# UltiMem64_v1.net
KiCad netlist of a schematic drawn in EAGLE
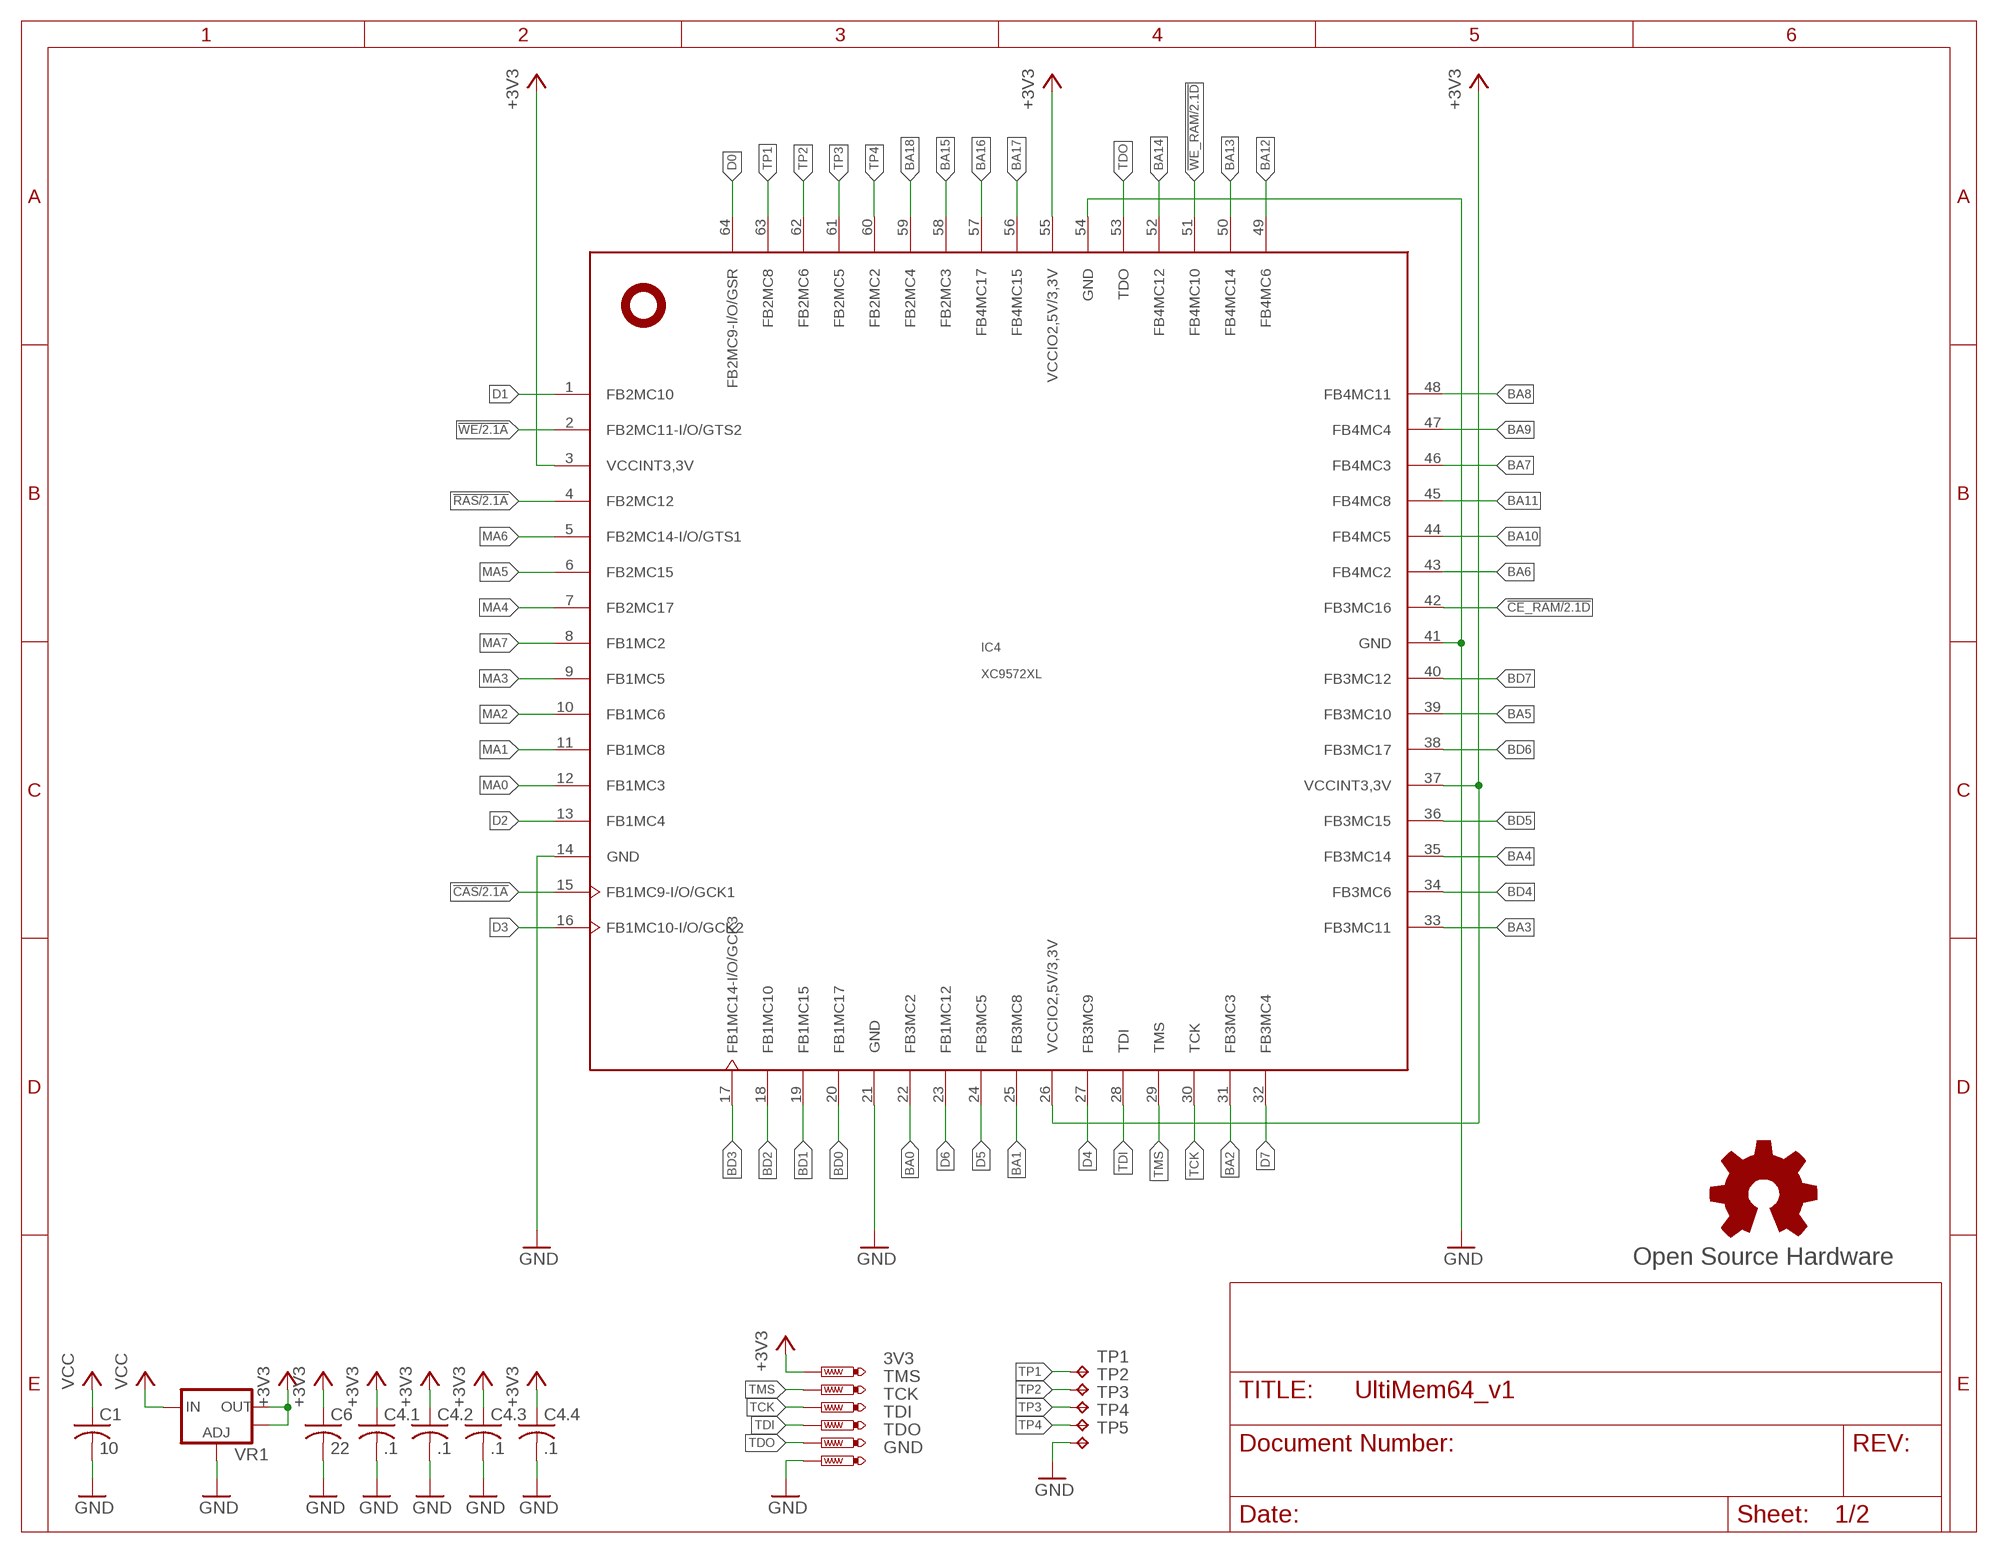
[diagram p0: schematic, sheet 1]
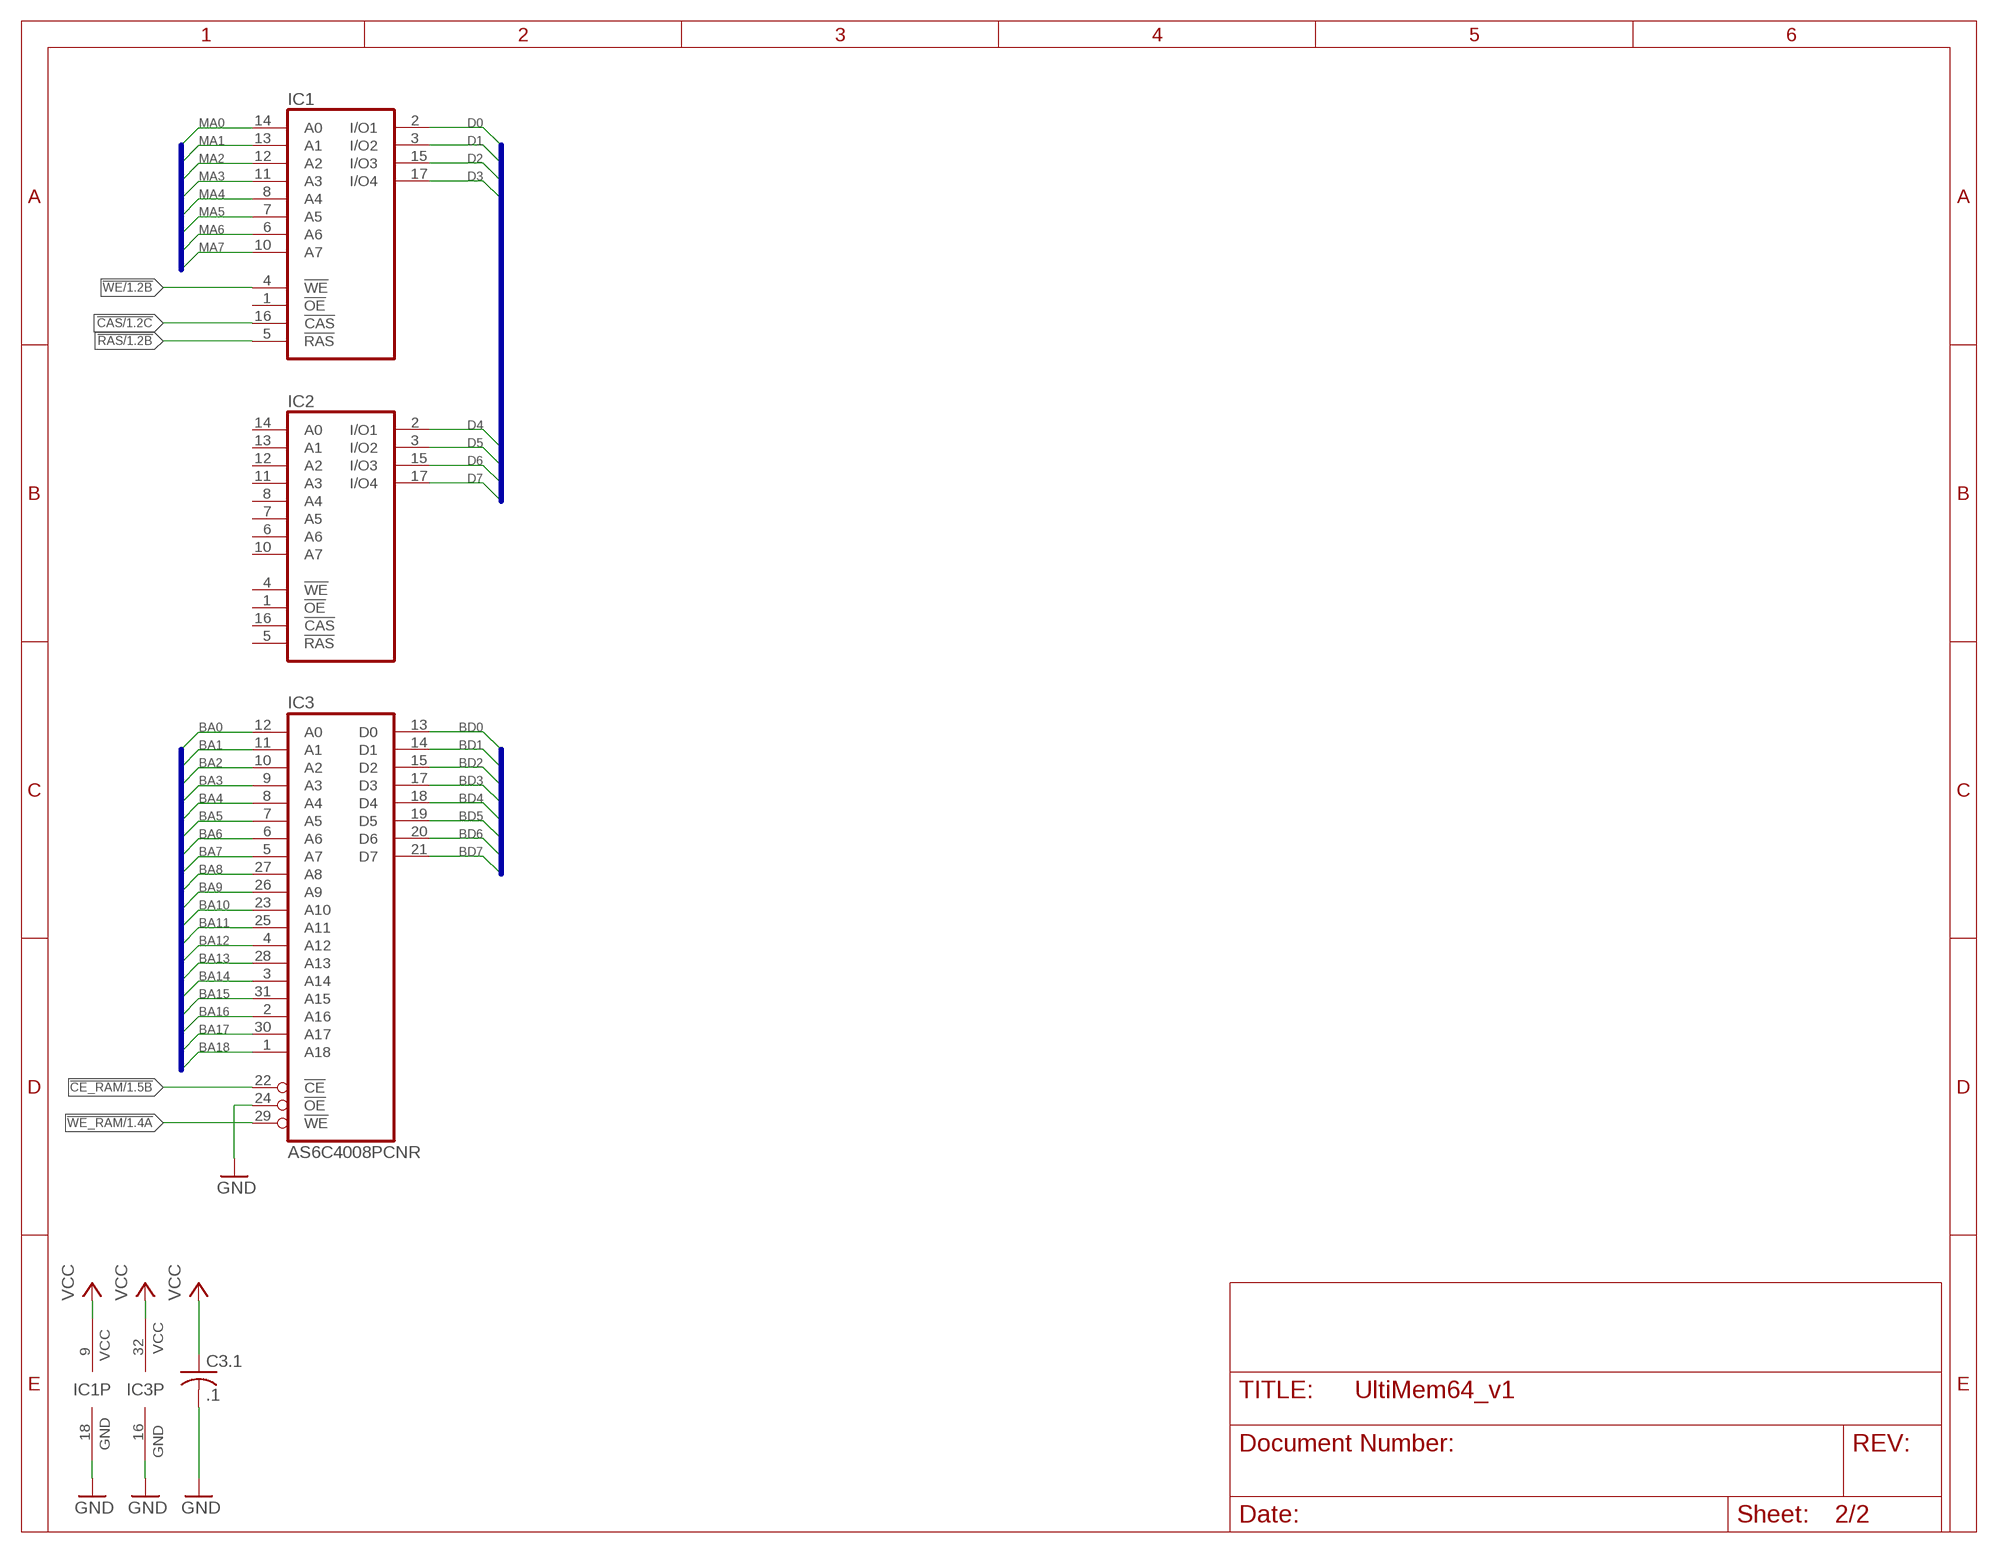
[diagram p1: schematic, sheet 2]

(export (version "E")
  (design (tool "Eeschema 10.0.6"))
  (components
    (comp (ref "3V3")
      (value "PTR1TP08R")
      (footprint "eagle-import:TP08R")
      (libsource (lib "eagle-import") (part "PTR1TP08R"))
    )
    (comp (ref "C1")
      (value "10")
      (footprint "eagle-import:C0805")
      (libsource (lib "eagle-import") (part "C-USC0805"))
    )
    (comp (ref "C4.1")
      (value ".1")
      (footprint "eagle-import:C0402")
      (libsource (lib "eagle-import") (part "C-USC0402"))
    )
    (comp (ref "C4.2")
      (value ".1")
      (footprint "eagle-import:C0402")
      (libsource (lib "eagle-import") (part "C-USC0402"))
    )
    (comp (ref "C4.3")
      (value ".1")
      (footprint "eagle-import:C0402")
      (libsource (lib "eagle-import") (part "C-USC0402"))
    )
    (comp (ref "C4.4")
      (value ".1")
      (footprint "eagle-import:C0402")
      (libsource (lib "eagle-import") (part "C-USC0402"))
    )
    (comp (ref "C6")
      (value "22")
      (footprint "eagle-import:C0805")
      (libsource (lib "eagle-import") (part "C-USC0805"))
    )
    (comp (ref "GND")
      (value "PTR1TP08R")
      (footprint "eagle-import:TP08R")
      (libsource (lib "eagle-import") (part "PTR1TP08R"))
    )
    (comp (ref "GOLD_ORB_SM1")
      (value "Open Source Hardware")
      (footprint "eagle-import:OSHW_5MM")
      (libsource (lib "eagle-import") (part "OSHWLOGOLOGO5MM"))
    )
    (comp (ref "IC4")
      (value "XC9572XL")
      (footprint "eagle-import:VQFP64")
      (libsource (lib "eagle-import") (part "XC9572XLVQG64"))
    )
    (comp (ref "TCK")
      (value "PTR1TP08R")
      (footprint "eagle-import:TP08R")
      (libsource (lib "eagle-import") (part "PTR1TP08R"))
    )
    (comp (ref "TDI")
      (value "PTR1TP08R")
      (footprint "eagle-import:TP08R")
      (libsource (lib "eagle-import") (part "PTR1TP08R"))
    )
    (comp (ref "TDO")
      (value "PTR1TP08R")
      (footprint "eagle-import:TP08R")
      (libsource (lib "eagle-import") (part "PTR1TP08R"))
    )
    (comp (ref "TMS")
      (value "PTR1TP08R")
      (footprint "eagle-import:TP08R")
      (libsource (lib "eagle-import") (part "PTR1TP08R"))
    )
    (comp (ref "TP1")
      (value "TPPAD1-13")
      (footprint "eagle-import:P1-13")
      (libsource (lib "eagle-import") (part "TPPAD1-13"))
    )
    (comp (ref "TP2")
      (value "TPPAD1-13")
      (footprint "eagle-import:P1-13")
      (libsource (lib "eagle-import") (part "TPPAD1-13"))
    )
    (comp (ref "TP3")
      (value "TPPAD1-13")
      (footprint "eagle-import:P1-13")
      (libsource (lib "eagle-import") (part "TPPAD1-13"))
    )
    (comp (ref "TP4")
      (value "TPPAD1-13")
      (footprint "eagle-import:P1-13")
      (libsource (lib "eagle-import") (part "TPPAD1-13"))
    )
    (comp (ref "TP5")
      (value "TPPAD1-13")
      (footprint "eagle-import:P1-13")
      (libsource (lib "eagle-import") (part "TPPAD1-13"))
    )
    (comp (ref "VR1")
      (value "V_REG_LM1117SOT223")
      (footprint "eagle-import:SOT223")
      (libsource (lib "eagle-import") (part "V_REG_LM1117SOT223"))
    )
    (comp (ref "C3.1")
      (value ".1")
      (footprint "eagle-import:C0402")
      (libsource (lib "eagle-import") (part "C-USC0402"))
    )
    (comp (ref "IC1")
      (value "41464C-HDR")
      (footprint "eagle-import:DIL18_REV")
      (libsource (lib "eagle-import") (part "41464C-HDR"))
    )
    (comp (ref "IC2")
      (value "41464C-HDR")
      (footprint "eagle-import:DIL18_REV")
      (libsource (lib "eagle-import") (part "41464C-HDR"))
    )
    (comp (ref "IC3")
      (value "AS6C4008PCNR")
      (footprint "eagle-import:DIL32-RP")
      (libsource (lib "eagle-import") (part "AS6C4008PCNR"))
    )
  )
  (nets
    (net (code "1") (name "+3V3") (class "Default")
      (node (ref "3V3") (pin "TP") (pinfunction "TP_TP") (pintype "input"))
      (node (ref "C4.1") (pin "1") (pinfunction "1_1") (pintype "passive"))
      (node (ref "C4.2") (pin "1") (pinfunction "1_1") (pintype "passive"))
      (node (ref "C4.3") (pin "1") (pinfunction "1_1") (pintype "passive"))
      (node (ref "C4.4") (pin "1") (pinfunction "1_1") (pintype "passive"))
      (node (ref "C6") (pin "1") (pinfunction "1_1") (pintype "passive"))
      (node (ref "IC4") (pin "26") (pinfunction "VCCIO2,5V/3,3V_26") (pintype "power_in"))
      (node (ref "IC4") (pin "3") (pinfunction "VCCINT3,3V_3") (pintype "power_in"))
      (node (ref "IC4") (pin "37") (pinfunction "VCCINT3,3V_37") (pintype "power_in"))
      (node (ref "IC4") (pin "55") (pinfunction "VCCIO2,5V/3,3V_55") (pintype "power_in"))
      (node (ref "VR1") (pin "2") (pinfunction "OUT_2") (pintype "output"))
      (node (ref "VR1") (pin "4") (pinfunction "OUT_4") (pintype "output"))
    )
    (net (code "2") (name "BA0") (class "Default")
      (node (ref "IC3") (pin "12") (pinfunction "A0_12") (pintype "input"))
      (node (ref "IC4") (pin "22") (pinfunction "FB3MC2_22") (pintype "bidirectional"))
    )
    (net (code "3") (name "BA1") (class "Default")
      (node (ref "IC3") (pin "11") (pinfunction "A1_11") (pintype "input"))
      (node (ref "IC4") (pin "25") (pinfunction "FB3MC8_25") (pintype "bidirectional"))
    )
    (net (code "4") (name "BA2") (class "Default")
      (node (ref "IC3") (pin "10") (pinfunction "A2_10") (pintype "input"))
      (node (ref "IC4") (pin "31") (pinfunction "FB3MC3_31") (pintype "bidirectional"))
    )
    (net (code "5") (name "BA3") (class "Default")
      (node (ref "IC3") (pin "9") (pinfunction "A3_9") (pintype "input"))
      (node (ref "IC4") (pin "33") (pinfunction "FB3MC11_33") (pintype "bidirectional"))
    )
    (net (code "6") (name "BA4") (class "Default")
      (node (ref "IC3") (pin "8") (pinfunction "A4_8") (pintype "input"))
      (node (ref "IC4") (pin "35") (pinfunction "FB3MC14_35") (pintype "bidirectional"))
    )
    (net (code "7") (name "BA5") (class "Default")
      (node (ref "IC3") (pin "7") (pinfunction "A5_7") (pintype "input"))
      (node (ref "IC4") (pin "39") (pinfunction "FB3MC10_39") (pintype "bidirectional"))
    )
    (net (code "8") (name "BA6") (class "Default")
      (node (ref "IC3") (pin "6") (pinfunction "A6_6") (pintype "input"))
      (node (ref "IC4") (pin "43") (pinfunction "FB4MC2_43") (pintype "bidirectional"))
    )
    (net (code "9") (name "BA7") (class "Default")
      (node (ref "IC3") (pin "5") (pinfunction "A7_5") (pintype "input"))
      (node (ref "IC4") (pin "46") (pinfunction "FB4MC3_46") (pintype "bidirectional"))
    )
    (net (code "10") (name "BA8") (class "Default")
      (node (ref "IC3") (pin "27") (pinfunction "A8_27") (pintype "input"))
      (node (ref "IC4") (pin "48") (pinfunction "FB4MC11_48") (pintype "bidirectional"))
    )
    (net (code "11") (name "BA9") (class "Default")
      (node (ref "IC3") (pin "26") (pinfunction "A9_26") (pintype "input"))
      (node (ref "IC4") (pin "47") (pinfunction "FB4MC4_47") (pintype "bidirectional"))
    )
    (net (code "12") (name "BA10") (class "Default")
      (node (ref "IC3") (pin "23") (pinfunction "A10_23") (pintype "input"))
      (node (ref "IC4") (pin "44") (pinfunction "FB4MC5_44") (pintype "bidirectional"))
    )
    (net (code "13") (name "BA11") (class "Default")
      (node (ref "IC3") (pin "25") (pinfunction "A11_25") (pintype "input"))
      (node (ref "IC4") (pin "45") (pinfunction "FB4MC8_45") (pintype "bidirectional"))
    )
    (net (code "14") (name "BA12") (class "Default")
      (node (ref "IC3") (pin "4") (pinfunction "A12_4") (pintype "input"))
      (node (ref "IC4") (pin "49") (pinfunction "FB4MC6_49") (pintype "bidirectional"))
    )
    (net (code "15") (name "BA13") (class "Default")
      (node (ref "IC3") (pin "28") (pinfunction "A13_28") (pintype "input"))
      (node (ref "IC4") (pin "50") (pinfunction "FB4MC14_50") (pintype "bidirectional"))
    )
    (net (code "16") (name "BA14") (class "Default")
      (node (ref "IC3") (pin "3") (pinfunction "A14_3") (pintype "input"))
      (node (ref "IC4") (pin "52") (pinfunction "FB4MC12_52") (pintype "bidirectional"))
    )
    (net (code "17") (name "BA15") (class "Default")
      (node (ref "IC3") (pin "31") (pinfunction "A15_31") (pintype "input"))
      (node (ref "IC4") (pin "58") (pinfunction "FB2MC3_58") (pintype "bidirectional"))
    )
    (net (code "18") (name "BA16") (class "Default")
      (node (ref "IC3") (pin "2") (pinfunction "A16_2") (pintype "input"))
      (node (ref "IC4") (pin "57") (pinfunction "FB4MC17_57") (pintype "bidirectional"))
    )
    (net (code "19") (name "BA17") (class "Default")
      (node (ref "IC3") (pin "30") (pinfunction "A17_30") (pintype "input"))
      (node (ref "IC4") (pin "56") (pinfunction "FB4MC15_56") (pintype "bidirectional"))
    )
    (net (code "20") (name "BA18") (class "Default")
      (node (ref "IC3") (pin "1") (pinfunction "A18_1") (pintype "input"))
      (node (ref "IC4") (pin "59") (pinfunction "FB2MC4_59") (pintype "bidirectional"))
    )
    (net (code "21") (name "BD0") (class "Default")
      (node (ref "IC3") (pin "13") (pinfunction "D0_13") (pintype "bidirectional"))
      (node (ref "IC4") (pin "20") (pinfunction "FB1MC17_20") (pintype "bidirectional"))
    )
    (net (code "22") (name "BD1") (class "Default")
      (node (ref "IC3") (pin "14") (pinfunction "D1_14") (pintype "bidirectional"))
      (node (ref "IC4") (pin "19") (pinfunction "FB1MC15_19") (pintype "bidirectional"))
    )
    (net (code "23") (name "BD2") (class "Default")
      (node (ref "IC3") (pin "15") (pinfunction "D2_15") (pintype "bidirectional"))
      (node (ref "IC4") (pin "18") (pinfunction "FB1MC10_18") (pintype "bidirectional"))
    )
    (net (code "24") (name "BD3") (class "Default")
      (node (ref "IC3") (pin "17") (pinfunction "D3_17") (pintype "bidirectional"))
      (node (ref "IC4") (pin "17") (pinfunction "FB1MC14-I/O/GCK3_17") (pintype "bidirectional"))
    )
    (net (code "25") (name "BD4") (class "Default")
      (node (ref "IC3") (pin "18") (pinfunction "D4_18") (pintype "bidirectional"))
      (node (ref "IC4") (pin "34") (pinfunction "FB3MC6_34") (pintype "bidirectional"))
    )
    (net (code "26") (name "BD5") (class "Default")
      (node (ref "IC3") (pin "19") (pinfunction "D5_19") (pintype "bidirectional"))
      (node (ref "IC4") (pin "36") (pinfunction "FB3MC15_36") (pintype "bidirectional"))
    )
    (net (code "27") (name "BD6") (class "Default")
      (node (ref "IC3") (pin "20") (pinfunction "D6_20") (pintype "bidirectional"))
      (node (ref "IC4") (pin "38") (pinfunction "FB3MC17_38") (pintype "bidirectional"))
    )
    (net (code "28") (name "BD7") (class "Default")
      (node (ref "IC3") (pin "21") (pinfunction "D7_21") (pintype "bidirectional"))
      (node (ref "IC4") (pin "40") (pinfunction "FB3MC12_40") (pintype "bidirectional"))
    )
    (net (code "29") (name "D0") (class "Default")
      (node (ref "IC1") (pin "2") (pinfunction "I/O1_2") (pintype "bidirectional"))
      (node (ref "IC4") (pin "64") (pinfunction "FB2MC9-I/O/GSR_64") (pintype "bidirectional"))
    )
    (net (code "30") (name "D1") (class "Default")
      (node (ref "IC1") (pin "3") (pinfunction "I/O2_3") (pintype "bidirectional"))
      (node (ref "IC4") (pin "1") (pinfunction "FB2MC10_1") (pintype "bidirectional"))
    )
    (net (code "31") (name "D2") (class "Default")
      (node (ref "IC1") (pin "15") (pinfunction "I/O3_15") (pintype "bidirectional"))
      (node (ref "IC4") (pin "13") (pinfunction "FB1MC4_13") (pintype "bidirectional"))
    )
    (net (code "32") (name "D3") (class "Default")
      (node (ref "IC1") (pin "17") (pinfunction "I/O4_17") (pintype "bidirectional"))
      (node (ref "IC4") (pin "16") (pinfunction "FB1MC10-I/O/GCK2_16") (pintype "bidirectional"))
    )
    (net (code "33") (name "D4") (class "Default")
      (node (ref "IC2") (pin "2") (pinfunction "I/O1_2") (pintype "bidirectional"))
      (node (ref "IC4") (pin "27") (pinfunction "FB3MC9_27") (pintype "bidirectional"))
    )
    (net (code "34") (name "D5") (class "Default")
      (node (ref "IC2") (pin "3") (pinfunction "I/O2_3") (pintype "bidirectional"))
      (node (ref "IC4") (pin "24") (pinfunction "FB3MC5_24") (pintype "bidirectional"))
    )
    (net (code "35") (name "D6") (class "Default")
      (node (ref "IC2") (pin "15") (pinfunction "I/O3_15") (pintype "bidirectional"))
      (node (ref "IC4") (pin "23") (pinfunction "FB1MC12_23") (pintype "bidirectional"))
    )
    (net (code "36") (name "D7") (class "Default")
      (node (ref "IC2") (pin "17") (pinfunction "I/O4_17") (pintype "bidirectional"))
      (node (ref "IC4") (pin "32") (pinfunction "FB3MC4_32") (pintype "bidirectional"))
    )
    (net (code "37") (name "GND") (class "Default")
      (node (ref "C1") (pin "2") (pinfunction "2_2") (pintype "passive"))
      (node (ref "C3.1") (pin "2") (pinfunction "2_2") (pintype "passive"))
      (node (ref "C4.1") (pin "2") (pinfunction "2_2") (pintype "passive"))
      (node (ref "C4.2") (pin "2") (pinfunction "2_2") (pintype "passive"))
      (node (ref "C4.3") (pin "2") (pinfunction "2_2") (pintype "passive"))
      (node (ref "C4.4") (pin "2") (pinfunction "2_2") (pintype "passive"))
      (node (ref "C6") (pin "2") (pinfunction "2_2") (pintype "passive"))
      (node (ref "GND") (pin "TP") (pinfunction "TP_TP") (pintype "input"))
      (node (ref "IC1") (pin "18") (pinfunction "GND_18") (pintype "power_in"))
      (node (ref "IC3") (pin "16") (pinfunction "GND_16") (pintype "power_in"))
      (node (ref "IC3") (pin "24") (pinfunction "~{OE}_24") (pintype "input"))
      (node (ref "IC4") (pin "14") (pinfunction "GND_14") (pintype "power_in"))
      (node (ref "IC4") (pin "21") (pinfunction "GND_21") (pintype "power_in"))
      (node (ref "IC4") (pin "41") (pinfunction "GND_41") (pintype "power_in"))
      (node (ref "IC4") (pin "54") (pinfunction "GND_54") (pintype "power_in"))
      (node (ref "TP5") (pin "TP") (pinfunction "TP_TP") (pintype "input"))
      (node (ref "VR1") (pin "1") (pinfunction "ADJ_1") (pintype "input"))
    )
    (net (code "38") (name "MA0") (class "Default")
      (node (ref "IC1") (pin "14") (pinfunction "A0_14") (pintype "input"))
      (node (ref "IC4") (pin "12") (pinfunction "FB1MC3_12") (pintype "bidirectional"))
    )
    (net (code "39") (name "MA1") (class "Default")
      (node (ref "IC1") (pin "13") (pinfunction "A1_13") (pintype "input"))
      (node (ref "IC4") (pin "11") (pinfunction "FB1MC8_11") (pintype "bidirectional"))
    )
    (net (code "40") (name "MA2") (class "Default")
      (node (ref "IC1") (pin "12") (pinfunction "A2_12") (pintype "input"))
      (node (ref "IC4") (pin "10") (pinfunction "FB1MC6_10") (pintype "bidirectional"))
    )
    (net (code "41") (name "MA3") (class "Default")
      (node (ref "IC1") (pin "11") (pinfunction "A3_11") (pintype "input"))
      (node (ref "IC4") (pin "9") (pinfunction "FB1MC5_9") (pintype "bidirectional"))
    )
    (net (code "42") (name "MA4") (class "Default")
      (node (ref "IC1") (pin "8") (pinfunction "A4_8") (pintype "input"))
      (node (ref "IC4") (pin "7") (pinfunction "FB2MC17_7") (pintype "bidirectional"))
    )
    (net (code "43") (name "MA5") (class "Default")
      (node (ref "IC1") (pin "7") (pinfunction "A5_7") (pintype "input"))
      (node (ref "IC4") (pin "6") (pinfunction "FB2MC15_6") (pintype "bidirectional"))
    )
    (net (code "44") (name "MA6") (class "Default")
      (node (ref "IC1") (pin "6") (pinfunction "A6_6") (pintype "input"))
      (node (ref "IC4") (pin "5") (pinfunction "FB2MC14-I/O/GTS1_5") (pintype "bidirectional"))
    )
    (net (code "45") (name "MA7") (class "Default")
      (node (ref "IC1") (pin "10") (pinfunction "A7_10") (pintype "input"))
      (node (ref "IC4") (pin "8") (pinfunction "FB1MC2_8") (pintype "bidirectional"))
    )
    (net (code "46") (name "TCK") (class "Default")
      (node (ref "IC4") (pin "30") (pinfunction "TCK_30") (pintype "bidirectional"))
      (node (ref "TCK") (pin "TP") (pinfunction "TP_TP") (pintype "input"))
    )
    (net (code "47") (name "TDI") (class "Default")
      (node (ref "IC4") (pin "28") (pinfunction "TDI_28") (pintype "bidirectional"))
      (node (ref "TDI") (pin "TP") (pinfunction "TP_TP") (pintype "input"))
    )
    (net (code "48") (name "TDO") (class "Default")
      (node (ref "IC4") (pin "53") (pinfunction "TDO_53") (pintype "bidirectional"))
      (node (ref "TDO") (pin "TP") (pinfunction "TP_TP") (pintype "input"))
    )
    (net (code "49") (name "TMS") (class "Default")
      (node (ref "IC4") (pin "29") (pinfunction "TMS_29") (pintype "bidirectional"))
      (node (ref "TMS") (pin "TP") (pinfunction "TP_TP") (pintype "input"))
    )
    (net (code "50") (name "TP1") (class "Default")
      (node (ref "IC4") (pin "63") (pinfunction "FB2MC8_63") (pintype "bidirectional"))
      (node (ref "TP1") (pin "TP") (pinfunction "TP_TP") (pintype "input"))
    )
    (net (code "51") (name "TP2") (class "Default")
      (node (ref "IC4") (pin "62") (pinfunction "FB2MC6_62") (pintype "bidirectional"))
      (node (ref "TP2") (pin "TP") (pinfunction "TP_TP") (pintype "input"))
    )
    (net (code "52") (name "TP3") (class "Default")
      (node (ref "IC4") (pin "61") (pinfunction "FB2MC5_61") (pintype "bidirectional"))
      (node (ref "TP3") (pin "TP") (pinfunction "TP_TP") (pintype "input"))
    )
    (net (code "53") (name "TP4") (class "Default")
      (node (ref "IC4") (pin "60") (pinfunction "FB2MC2_60") (pintype "bidirectional"))
      (node (ref "TP4") (pin "TP") (pinfunction "TP_TP") (pintype "input"))
    )
    (net (code "54") (name "VCC") (class "Default")
      (node (ref "C1") (pin "1") (pinfunction "1_1") (pintype "passive"))
      (node (ref "C3.1") (pin "1") (pinfunction "1_1") (pintype "passive"))
      (node (ref "IC1") (pin "9") (pinfunction "VCC_9") (pintype "power_in"))
      (node (ref "IC3") (pin "32") (pinfunction "VCC_32") (pintype "power_in"))
      (node (ref "VR1") (pin "3") (pinfunction "IN_3") (pintype "input"))
    )
    (net (code "55") (name "unconnected-(IC1A-~{OE}-Pad1)") (class "Default")
      (node (ref "IC1") (pin "1") (pinfunction "~{OE}_1") (pintype "input"))
    )
    (net (code "56") (name "unconnected-(IC2A-A0-Pad14)") (class "Default")
      (node (ref "IC2") (pin "14") (pinfunction "A0_14") (pintype "input"))
    )
    (net (code "57") (name "unconnected-(IC2A-A1-Pad13)") (class "Default")
      (node (ref "IC2") (pin "13") (pinfunction "A1_13") (pintype "input"))
    )
    (net (code "58") (name "unconnected-(IC2A-A2-Pad12)") (class "Default")
      (node (ref "IC2") (pin "12") (pinfunction "A2_12") (pintype "input"))
    )
    (net (code "59") (name "unconnected-(IC2A-A3-Pad11)") (class "Default")
      (node (ref "IC2") (pin "11") (pinfunction "A3_11") (pintype "input"))
    )
    (net (code "60") (name "unconnected-(IC2A-A4-Pad8)") (class "Default")
      (node (ref "IC2") (pin "8") (pinfunction "A4_8") (pintype "input"))
    )
    (net (code "61") (name "unconnected-(IC2A-A5-Pad7)") (class "Default")
      (node (ref "IC2") (pin "7") (pinfunction "A5_7") (pintype "input"))
    )
    (net (code "62") (name "unconnected-(IC2A-A6-Pad6)") (class "Default")
      (node (ref "IC2") (pin "6") (pinfunction "A6_6") (pintype "input"))
    )
    (net (code "63") (name "unconnected-(IC2A-A7-Pad10)") (class "Default")
      (node (ref "IC2") (pin "10") (pinfunction "A7_10") (pintype "input"))
    )
    (net (code "64") (name "unconnected-(IC2A-~{CAS}-Pad16)") (class "Default")
      (node (ref "IC2") (pin "16") (pinfunction "~{CAS}_16") (pintype "input"))
    )
    (net (code "65") (name "unconnected-(IC2A-~{OE}-Pad1)") (class "Default")
      (node (ref "IC2") (pin "1") (pinfunction "~{OE}_1") (pintype "input"))
    )
    (net (code "66") (name "unconnected-(IC2A-~{RAS}-Pad5)") (class "Default")
      (node (ref "IC2") (pin "5") (pinfunction "~{RAS}_5") (pintype "input"))
    )
    (net (code "67") (name "unconnected-(IC2A-~{WE}-Pad4)") (class "Default")
      (node (ref "IC2") (pin "4") (pinfunction "~{WE}_4") (pintype "input"))
    )
    (net (code "68") (name "~{CAS}") (class "Default")
      (node (ref "IC1") (pin "16") (pinfunction "~{CAS}_16") (pintype "input"))
      (node (ref "IC4") (pin "15") (pinfunction "FB1MC9-I/O/GCK1_15") (pintype "bidirectional"))
    )
    (net (code "69") (name "~{CE_RAM}") (class "Default")
      (node (ref "IC3") (pin "22") (pinfunction "~{CE}_22") (pintype "input"))
      (node (ref "IC4") (pin "42") (pinfunction "FB3MC16_42") (pintype "bidirectional"))
    )
    (net (code "70") (name "~{RAS}") (class "Default")
      (node (ref "IC1") (pin "5") (pinfunction "~{RAS}_5") (pintype "input"))
      (node (ref "IC4") (pin "4") (pinfunction "FB2MC12_4") (pintype "bidirectional"))
    )
    (net (code "71") (name "~{WE_RAM}") (class "Default")
      (node (ref "IC3") (pin "29") (pinfunction "~{WE}_29") (pintype "input"))
      (node (ref "IC4") (pin "51") (pinfunction "FB4MC10_51") (pintype "bidirectional"))
    )
    (net (code "72") (name "~{WE}") (class "Default")
      (node (ref "IC1") (pin "4") (pinfunction "~{WE}_4") (pintype "input"))
      (node (ref "IC4") (pin "2") (pinfunction "FB2MC11-I/O/GTS2_2") (pintype "bidirectional"))
    )
  )
)
